# TSOC_ESP32S.net
KiCad netlist of a schematic drawn in EAGLE
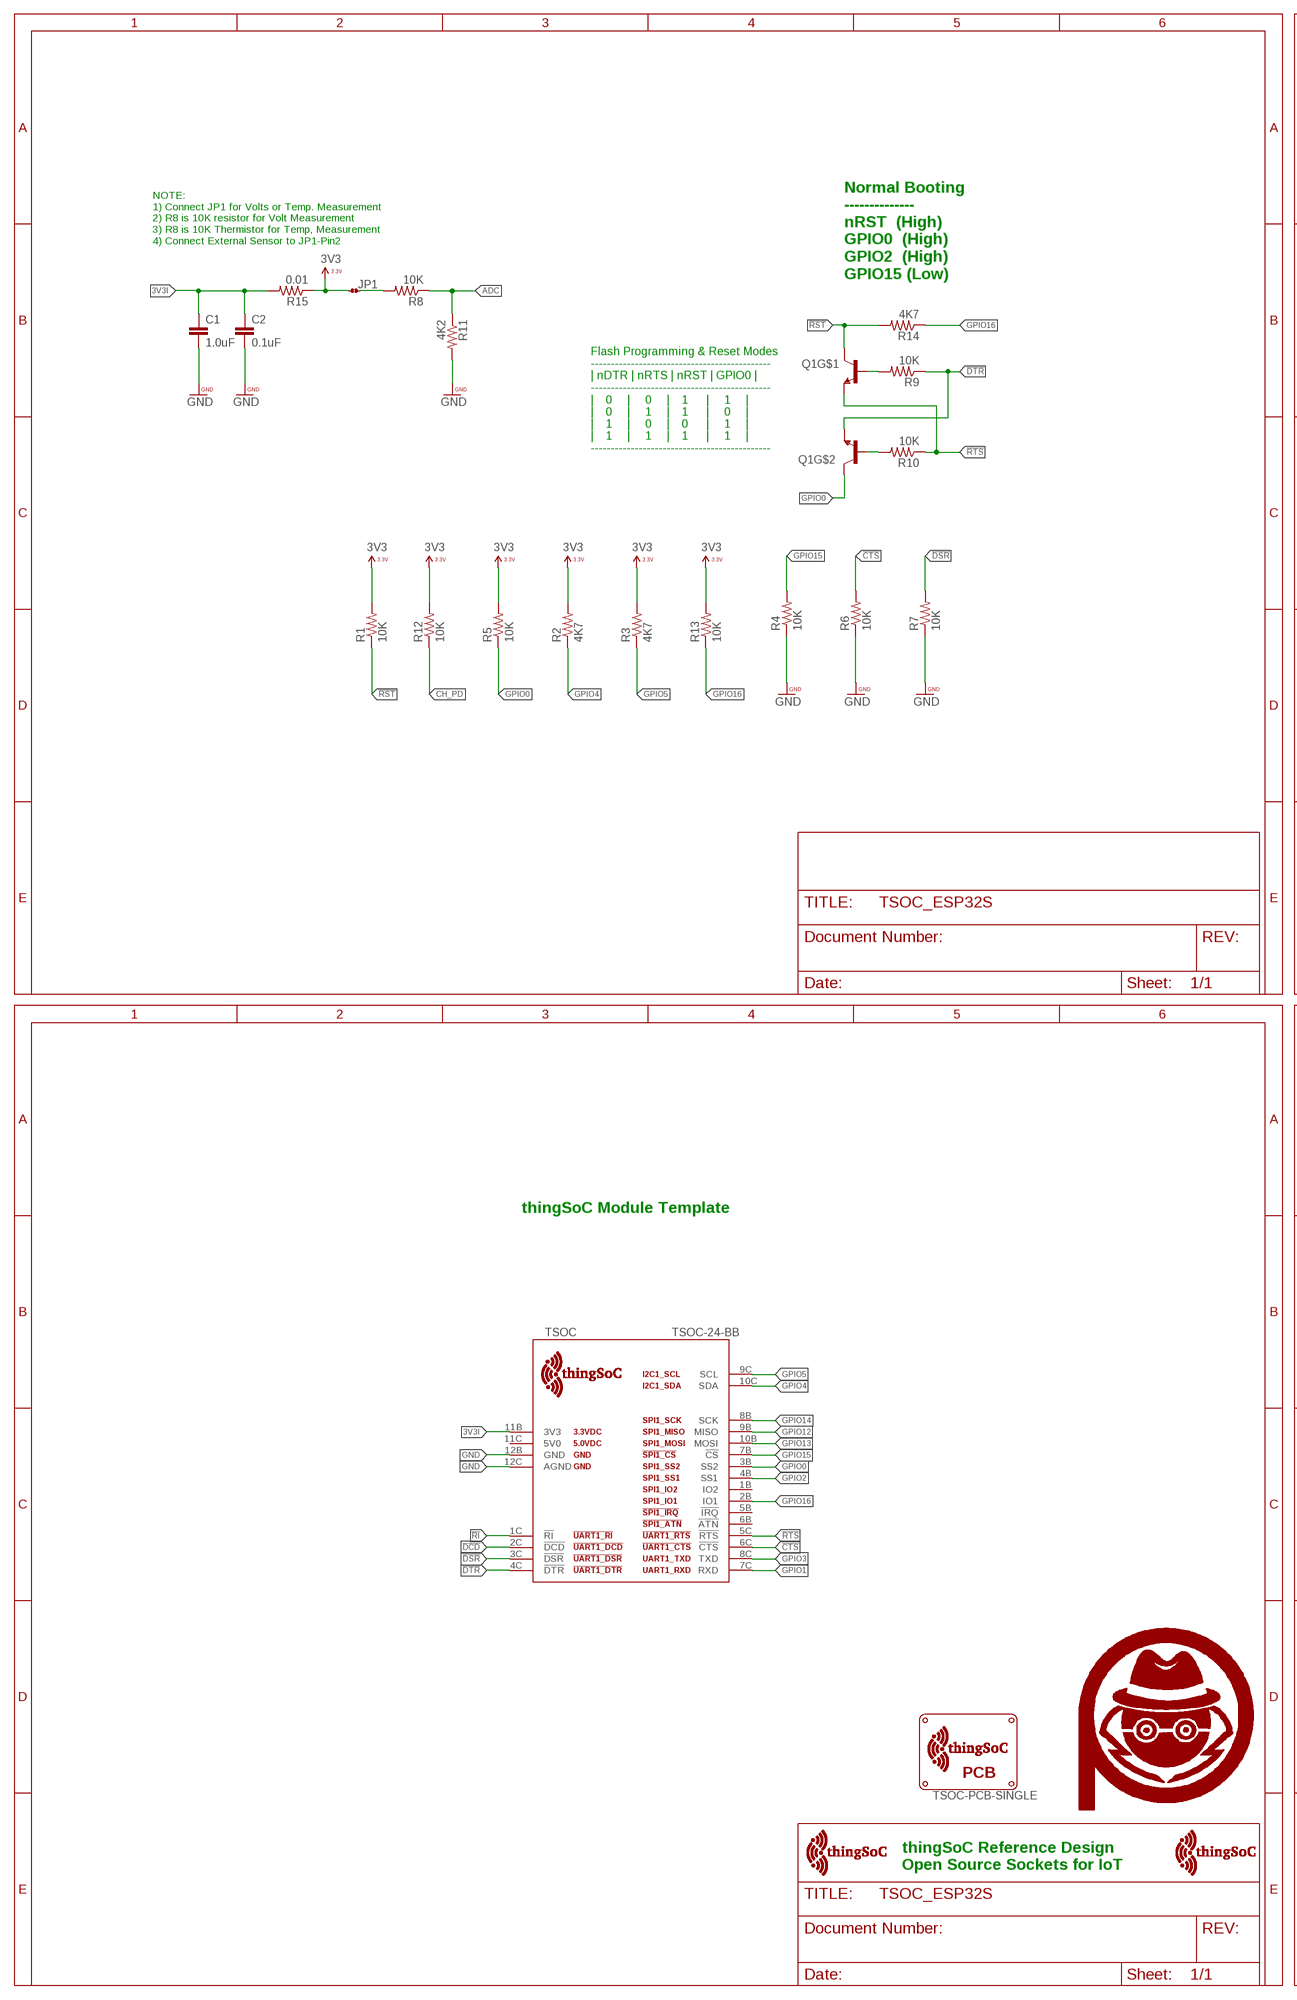
[diagram p0: schematic, sheet 1, part 1 of 2]
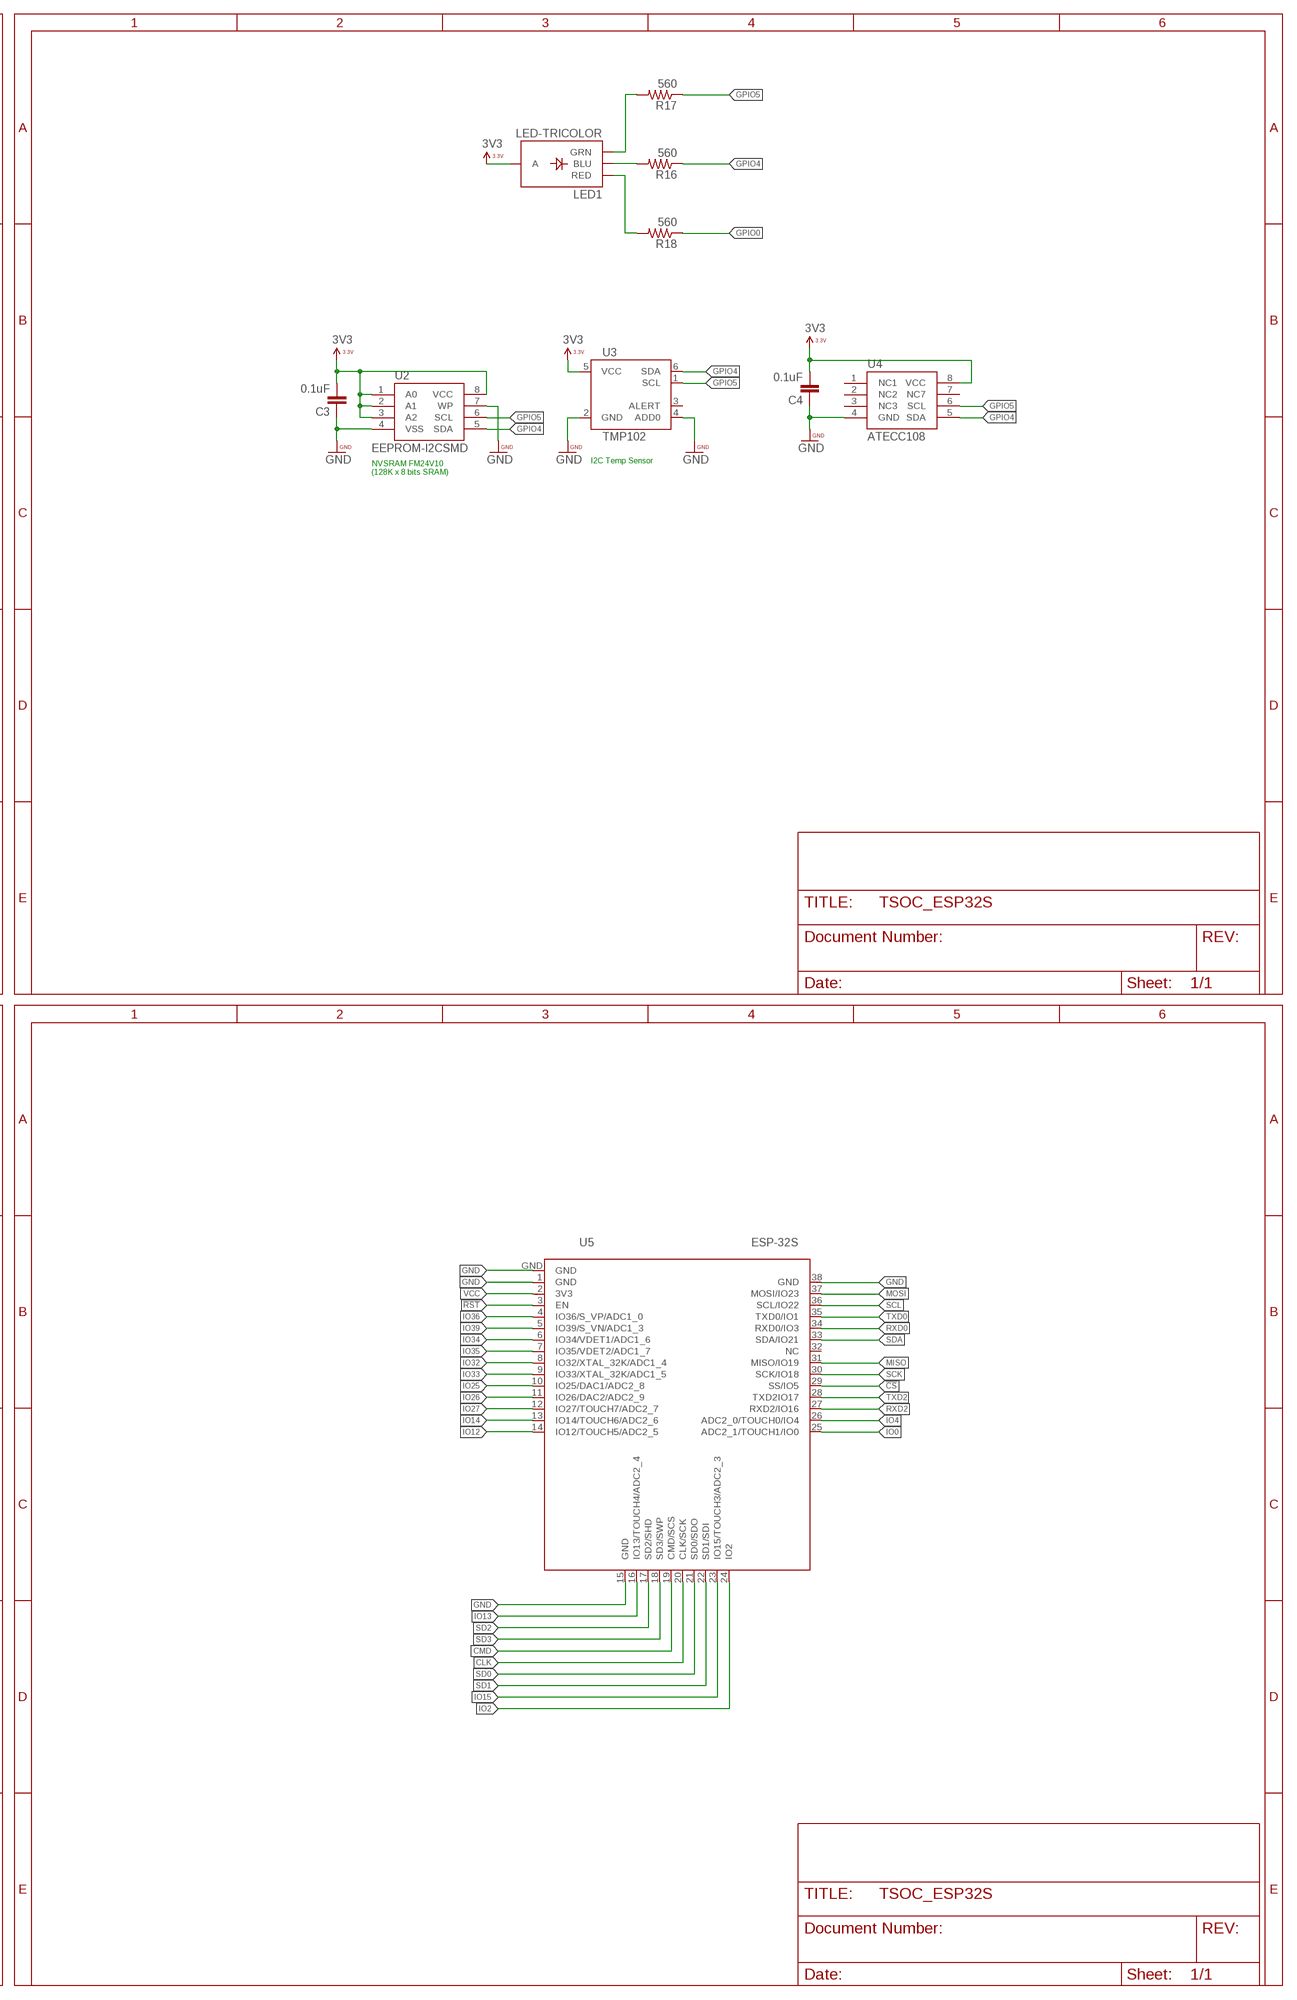
[diagram p1: schematic, sheet 1, part 2 of 2]

(export (version "E")
  (design (tool "Eeschema 10.0.6"))
  (components
    (comp (ref "C1")
      (value "1.0uF")
      (footprint "eagle-import:0402-CAP")
      (libsource (lib "eagle-import") (part "CAP0402-CAP"))
    )
    (comp (ref "C2")
      (value "0.1uF")
      (footprint "eagle-import:0402-CAP")
      (libsource (lib "eagle-import") (part "CAP0402-CAP"))
    )
    (comp (ref "C3")
      (value "0.1uF")
      (footprint "eagle-import:0402-CAP")
      (libsource (lib "eagle-import") (part "CAP0402-CAP"))
    )
    (comp (ref "C4")
      (value "0.1uF")
      (footprint "eagle-import:0402-CAP")
      (libsource (lib "eagle-import") (part "CAP0402-CAP"))
    )
    (comp (ref "JP1")
      (value "JMP-2-NO-0402")
      (footprint "eagle-import:JMP-2-NO-0402")
      (libsource (lib "eagle-import") (part "JMP-2-NO-0402"))
    )
    (comp (ref "LED1")
      (value "LED-TRICOLOR")
      (footprint "eagle-import:LED-TRICOLOR-SMD")
      (libsource (lib "eagle-import") (part "LED-TRICOLOR"))
    )
    (comp (ref "Q1")
      (value "MMBT2222A")
      (footprint "eagle-import:SOT363")
      (libsource (lib "eagle-import") (part "MMDT3904"))
    )
    (comp (ref "R1")
      (value "10K")
      (footprint "eagle-import:0402-RES")
      (libsource (lib "eagle-import") (part "RESISTOR0402"))
    )
    (comp (ref "R2")
      (value "4K7")
      (footprint "eagle-import:0402-RES")
      (libsource (lib "eagle-import") (part "RESISTOR0402"))
    )
    (comp (ref "R3")
      (value "4K7")
      (footprint "eagle-import:0402-RES")
      (libsource (lib "eagle-import") (part "RESISTOR0402"))
    )
    (comp (ref "R4")
      (value "10K")
      (footprint "eagle-import:0402-RES")
      (libsource (lib "eagle-import") (part "RESISTOR0402"))
    )
    (comp (ref "R5")
      (value "10K")
      (footprint "eagle-import:0402-RES")
      (libsource (lib "eagle-import") (part "RESISTOR0402"))
    )
    (comp (ref "R6")
      (value "10K")
      (footprint "eagle-import:0402-RES")
      (libsource (lib "eagle-import") (part "RESISTOR0402"))
    )
    (comp (ref "R7")
      (value "10K")
      (footprint "eagle-import:0402-RES")
      (libsource (lib "eagle-import") (part "RESISTOR0402"))
    )
    (comp (ref "R8")
      (value "10K")
      (footprint "eagle-import:0402-RES")
      (libsource (lib "eagle-import") (part "RESISTOR0402"))
    )
    (comp (ref "R9")
      (value "10K")
      (footprint "eagle-import:0402-RES")
      (libsource (lib "eagle-import") (part "RESISTOR0402"))
    )
    (comp (ref "R10")
      (value "10K")
      (footprint "eagle-import:0402-RES")
      (libsource (lib "eagle-import") (part "RESISTOR0402"))
    )
    (comp (ref "R11")
      (value "4K2")
      (footprint "eagle-import:0402-RES")
      (libsource (lib "eagle-import") (part "RESISTOR0402"))
    )
    (comp (ref "R12")
      (value "10K")
      (footprint "eagle-import:0402-RES")
      (libsource (lib "eagle-import") (part "RESISTOR0402"))
    )
    (comp (ref "R13")
      (value "10K")
      (footprint "eagle-import:0402-RES")
      (libsource (lib "eagle-import") (part "RESISTOR0402"))
    )
    (comp (ref "R14")
      (value "4K7")
      (footprint "eagle-import:0402-RES")
      (libsource (lib "eagle-import") (part "RESISTOR0402"))
    )
    (comp (ref "R15")
      (value "0.01")
      (footprint "eagle-import:0402-RES")
      (libsource (lib "eagle-import") (part "RESISTOR0402"))
    )
    (comp (ref "R16")
      (value "560")
      (footprint "eagle-import:0402-RES")
      (libsource (lib "eagle-import") (part "RESISTOR0402"))
    )
    (comp (ref "R17")
      (value "560")
      (footprint "eagle-import:0402-RES")
      (libsource (lib "eagle-import") (part "RESISTOR0402"))
    )
    (comp (ref "R18")
      (value "560")
      (footprint "eagle-import:0402-RES")
      (libsource (lib "eagle-import") (part "RESISTOR0402"))
    )
    (comp (ref "TSOC")
      (value "TSOC-24-BB")
      (footprint "eagle-import:TSOC-BB-S24")
      (libsource (lib "eagle-import") (part "TSOC-24-BB"))
    )
    (comp (ref "U$11")
      (value "PA_LOGO_SYMMED")
      (footprint "eagle-import:PA_LOGO_AGENT_MED_SYM")
      (libsource (lib "eagle-import") (part "PA_LOGO_SYMMED"))
    )
    (comp (ref "U$19")
      (value "TSOC-LOGO-MED")
      (footprint "eagle-import:TSOC-LOGO-MED")
      (libsource (lib "eagle-import") (part "TSOC-LOGO-MED"))
    )
    (comp (ref "U$20")
      (value "TSOC-LOGO-MED")
      (footprint "eagle-import:TSOC-LOGO-MED")
      (libsource (lib "eagle-import") (part "TSOC-LOGO-MED"))
    )
    (comp (ref "U$25")
      (value "TSOC-PCB-SINGLE")
      (footprint "eagle-import:TSOC-BB-BRD-DIM")
      (libsource (lib "eagle-import") (part "TSOC-PCB-SINGLE"))
    )
    (comp (ref "U2")
      (value "EEPROM-I2CSMD")
      (footprint "eagle-import:SO08")
      (libsource (lib "eagle-import") (part "EEPROM-I2CSMD"))
    )
    (comp (ref "U3")
      (value "TMP102")
      (footprint "eagle-import:SOT563")
      (libsource (lib "eagle-import") (part "TMP102"))
    )
    (comp (ref "U4")
      (value "ATECC108")
      (footprint "eagle-import:SOIC8")
      (libsource (lib "eagle-import") (part "ATECC108"))
    )
    (comp (ref "U5")
      (value "ESP-32S")
      (footprint "eagle-import:ESP-32S")
      (libsource (lib "eagle-import") (part "ESP-32S"))
    )
  )
  (nets
    (net (code "1") (name "/~{CS}") (class "Default")
      (node (ref "U5") (pin "29") (pinfunction "SS/IO5_29") (pintype "bidirectional"))
    )
    (net (code "2") (name "/~{CTS}") (class "Default")
      (node (ref "R6") (pin "2") (pinfunction "2_2") (pintype "passive"))
      (node (ref "TSOC") (pin "6C") (pinfunction "~{CTS}_6C") (pintype "bidirectional"))
    )
    (net (code "3") (name "/~{DCD}") (class "Default")
      (node (ref "TSOC") (pin "2C") (pinfunction "~{DCD}_2C") (pintype "bidirectional"))
    )
    (net (code "4") (name "/~{DSR}") (class "Default")
      (node (ref "R7") (pin "2") (pinfunction "2_2") (pintype "passive"))
      (node (ref "TSOC") (pin "3C") (pinfunction "~{DSR}_3C") (pintype "bidirectional"))
    )
    (net (code "5") (name "/~{DTR}") (class "Default")
      (node (ref "Q1") (pin "1") (pinfunction "E_1") (pintype "passive"))
      (node (ref "R9") (pin "1") (pinfunction "1_1") (pintype "passive"))
      (node (ref "TSOC") (pin "4C") (pinfunction "~{DTR}_4C") (pintype "bidirectional"))
    )
    (net (code "6") (name "/~{RI}") (class "Default")
      (node (ref "TSOC") (pin "1C") (pinfunction "~{RI}_1C") (pintype "bidirectional"))
    )
    (net (code "7") (name "/~{RST}") (class "Default")
      (node (ref "Q1") (pin "3") (pinfunction "C_3") (pintype "passive"))
      (node (ref "R1") (pin "1") (pinfunction "1_1") (pintype "passive"))
      (node (ref "R14") (pin "2") (pinfunction "2_2") (pintype "passive"))
      (node (ref "U5") (pin "3") (pinfunction "EN_3") (pintype "bidirectional"))
    )
    (net (code "8") (name "/~{RTS}") (class "Default")
      (node (ref "Q1") (pin "4") (pinfunction "E_4") (pintype "passive"))
      (node (ref "R10") (pin "1") (pinfunction "1_1") (pintype "passive"))
      (node (ref "TSOC") (pin "5C") (pinfunction "~{RTS}_5C") (pintype "bidirectional"))
    )
    (net (code "9") (name "3V3") (class "Default")
      (node (ref "C3") (pin "2") (pinfunction "2_2") (pintype "passive"))
      (node (ref "C4") (pin "2") (pinfunction "2_2") (pintype "passive"))
      (node (ref "JP1") (pin "1") (pinfunction "1_1") (pintype "passive"))
      (node (ref "LED1") (pin "A") (pinfunction "A_A") (pintype "bidirectional"))
      (node (ref "R1") (pin "2") (pinfunction "2_2") (pintype "passive"))
      (node (ref "R12") (pin "2") (pinfunction "2_2") (pintype "passive"))
      (node (ref "R13") (pin "2") (pinfunction "2_2") (pintype "passive"))
      (node (ref "R15") (pin "1") (pinfunction "1_1") (pintype "passive"))
      (node (ref "R2") (pin "2") (pinfunction "2_2") (pintype "passive"))
      (node (ref "R3") (pin "2") (pinfunction "2_2") (pintype "passive"))
      (node (ref "R5") (pin "2") (pinfunction "2_2") (pintype "passive"))
      (node (ref "U2") (pin "1") (pinfunction "A0_1") (pintype "bidirectional"))
      (node (ref "U2") (pin "2") (pinfunction "A1_2") (pintype "bidirectional"))
      (node (ref "U2") (pin "3") (pinfunction "A2_3") (pintype "bidirectional"))
      (node (ref "U2") (pin "8") (pinfunction "VCC_8") (pintype "power_in"))
      (node (ref "U3") (pin "5") (pinfunction "VCC_5") (pintype "bidirectional"))
      (node (ref "U4") (pin "8") (pinfunction "VCC_8") (pintype "power_in"))
    )
    (net (code "10") (name "3V3I") (class "Default")
      (node (ref "C1") (pin "1") (pinfunction "1_1") (pintype "passive"))
      (node (ref "C2") (pin "1") (pinfunction "1_1") (pintype "passive"))
      (node (ref "R15") (pin "2") (pinfunction "2_2") (pintype "passive"))
      (node (ref "TSOC") (pin "11B") (pinfunction "3V3_11B") (pintype "bidirectional"))
    )
    (net (code "11") (name "ADC") (class "Default")
      (node (ref "R11") (pin "1") (pinfunction "1_1") (pintype "passive"))
      (node (ref "R8") (pin "1") (pinfunction "1_1") (pintype "passive"))
    )
    (net (code "12") (name "CH_PD") (class "Default")
      (node (ref "R12") (pin "1") (pinfunction "1_1") (pintype "passive"))
    )
    (net (code "13") (name "CLK") (class "Default")
      (node (ref "U5") (pin "20") (pinfunction "CLK/SCK_20") (pintype "bidirectional"))
    )
    (net (code "14") (name "CMD") (class "Default")
      (node (ref "U5") (pin "19") (pinfunction "CMD/SCS_19") (pintype "bidirectional"))
    )
    (net (code "15") (name "GND") (class "Default")
      (node (ref "C1") (pin "2") (pinfunction "2_2") (pintype "passive"))
      (node (ref "C2") (pin "2") (pinfunction "2_2") (pintype "passive"))
      (node (ref "C3") (pin "1") (pinfunction "1_1") (pintype "passive"))
      (node (ref "C4") (pin "1") (pinfunction "1_1") (pintype "passive"))
      (node (ref "R11") (pin "2") (pinfunction "2_2") (pintype "passive"))
      (node (ref "R4") (pin "1") (pinfunction "1_1") (pintype "passive"))
      (node (ref "R6") (pin "1") (pinfunction "1_1") (pintype "passive"))
      (node (ref "R7") (pin "1") (pinfunction "1_1") (pintype "passive"))
      (node (ref "TSOC") (pin "12B") (pinfunction "GND_12B") (pintype "bidirectional"))
      (node (ref "TSOC") (pin "12C") (pinfunction "AGND_12C") (pintype "bidirectional"))
      (node (ref "U2") (pin "4") (pinfunction "VSS_4") (pintype "power_in"))
      (node (ref "U2") (pin "7") (pinfunction "WP_7") (pintype "bidirectional"))
      (node (ref "U3") (pin "2") (pinfunction "GND_2") (pintype "bidirectional"))
      (node (ref "U3") (pin "4") (pinfunction "ADD0_4") (pintype "bidirectional"))
      (node (ref "U4") (pin "4") (pinfunction "GND_4") (pintype "power_in"))
      (node (ref "U5") (pin "1") (pinfunction "GND_1") (pintype "bidirectional"))
      (node (ref "U5") (pin "15") (pinfunction "GND_15") (pintype "bidirectional"))
      (node (ref "U5") (pin "38") (pinfunction "GND_38") (pintype "bidirectional"))
      (node (ref "U5") (pin "GND") (pinfunction "GND_GND") (pintype "bidirectional"))
    )
    (net (code "16") (name "GPIO0") (class "Default")
      (node (ref "Q1") (pin "6") (pinfunction "C_6") (pintype "passive"))
      (node (ref "R18") (pin "1") (pinfunction "1_1") (pintype "passive"))
      (node (ref "R5") (pin "1") (pinfunction "1_1") (pintype "passive"))
      (node (ref "TSOC") (pin "3B") (pinfunction "SS2_3B") (pintype "bidirectional"))
    )
    (net (code "17") (name "GPIO1") (class "Default")
      (node (ref "TSOC") (pin "7C") (pinfunction "RXD_7C") (pintype "bidirectional"))
    )
    (net (code "18") (name "GPIO2") (class "Default")
      (node (ref "TSOC") (pin "4B") (pinfunction "SS1_4B") (pintype "bidirectional"))
    )
    (net (code "19") (name "GPIO3") (class "Default")
      (node (ref "TSOC") (pin "8C") (pinfunction "TXD_8C") (pintype "bidirectional"))
    )
    (net (code "20") (name "GPIO4") (class "Default")
      (node (ref "R16") (pin "1") (pinfunction "1_1") (pintype "passive"))
      (node (ref "R2") (pin "1") (pinfunction "1_1") (pintype "passive"))
      (node (ref "TSOC") (pin "10C") (pinfunction "SDA_10C") (pintype "bidirectional"))
      (node (ref "U2") (pin "5") (pinfunction "SDA_5") (pintype "bidirectional"))
      (node (ref "U3") (pin "6") (pinfunction "SDA_6") (pintype "bidirectional"))
      (node (ref "U4") (pin "5") (pinfunction "SDA_5") (pintype "bidirectional"))
    )
    (net (code "21") (name "GPIO5") (class "Default")
      (node (ref "R17") (pin "1") (pinfunction "1_1") (pintype "passive"))
      (node (ref "R3") (pin "1") (pinfunction "1_1") (pintype "passive"))
      (node (ref "TSOC") (pin "9C") (pinfunction "SCL_9C") (pintype "bidirectional"))
      (node (ref "U2") (pin "6") (pinfunction "SCL_6") (pintype "bidirectional"))
      (node (ref "U3") (pin "1") (pinfunction "SCL_1") (pintype "bidirectional"))
      (node (ref "U4") (pin "6") (pinfunction "SCL_6") (pintype "bidirectional"))
    )
    (net (code "22") (name "GPIO12") (class "Default")
      (node (ref "TSOC") (pin "9B") (pinfunction "MISO_9B") (pintype "bidirectional"))
    )
    (net (code "23") (name "GPIO13") (class "Default")
      (node (ref "TSOC") (pin "10B") (pinfunction "MOSI_10B") (pintype "bidirectional"))
    )
    (net (code "24") (name "GPIO14") (class "Default")
      (node (ref "TSOC") (pin "8B") (pinfunction "SCK_8B") (pintype "bidirectional"))
    )
    (net (code "25") (name "GPIO15") (class "Default")
      (node (ref "R4") (pin "2") (pinfunction "2_2") (pintype "passive"))
      (node (ref "TSOC") (pin "7B") (pinfunction "~{CS}_7B") (pintype "bidirectional"))
    )
    (net (code "26") (name "GPIO16") (class "Default")
      (node (ref "R13") (pin "1") (pinfunction "1_1") (pintype "passive"))
      (node (ref "R14") (pin "1") (pinfunction "1_1") (pintype "passive"))
      (node (ref "TSOC") (pin "2B") (pinfunction "IO1_2B") (pintype "bidirectional"))
    )
    (net (code "27") (name "IO0") (class "Default")
      (node (ref "U5") (pin "25") (pinfunction "ADC2_1/TOUCH1/IO0_25") (pintype "bidirectional"))
    )
    (net (code "28") (name "IO2") (class "Default")
      (node (ref "U5") (pin "24") (pinfunction "IO2_24") (pintype "bidirectional"))
    )
    (net (code "29") (name "IO4") (class "Default")
      (node (ref "U5") (pin "26") (pinfunction "ADC2_0/TOUCH0/IO4_26") (pintype "bidirectional"))
    )
    (net (code "30") (name "IO12") (class "Default")
      (node (ref "U5") (pin "14") (pinfunction "IO12/TOUCH5/ADC2_5_14") (pintype "bidirectional"))
    )
    (net (code "31") (name "IO13") (class "Default")
      (node (ref "U5") (pin "16") (pinfunction "IO13/TOUCH4/ADC2_4_16") (pintype "bidirectional"))
    )
    (net (code "32") (name "IO14") (class "Default")
      (node (ref "U5") (pin "13") (pinfunction "IO14/TOUCH6/ADC2_6_13") (pintype "bidirectional"))
    )
    (net (code "33") (name "IO15") (class "Default")
      (node (ref "U5") (pin "23") (pinfunction "IO15/TOUCH3/ADC2_3_23") (pintype "bidirectional"))
    )
    (net (code "34") (name "IO25") (class "Default")
      (node (ref "U5") (pin "10") (pinfunction "IO25/DAC1/ADC2_8_10") (pintype "bidirectional"))
    )
    (net (code "35") (name "IO26") (class "Default")
      (node (ref "U5") (pin "11") (pinfunction "IO26/DAC2/ADC2_9_11") (pintype "bidirectional"))
    )
    (net (code "36") (name "IO27") (class "Default")
      (node (ref "U5") (pin "12") (pinfunction "IO27/TOUCH7/ADC2_7_12") (pintype "bidirectional"))
    )
    (net (code "37") (name "IO32") (class "Default")
      (node (ref "U5") (pin "8") (pinfunction "IO32/XTAL_32K/ADC1_4_8") (pintype "bidirectional"))
    )
    (net (code "38") (name "IO33") (class "Default")
      (node (ref "U5") (pin "9") (pinfunction "IO33/XTAL_32K/ADC1_5_9") (pintype "bidirectional"))
    )
    (net (code "39") (name "IO34") (class "Default")
      (node (ref "U5") (pin "6") (pinfunction "IO34/VDET1/ADC1_6_6") (pintype "bidirectional"))
    )
    (net (code "40") (name "IO35") (class "Default")
      (node (ref "U5") (pin "7") (pinfunction "IO35/VDET2/ADC1_7_7") (pintype "bidirectional"))
    )
    (net (code "41") (name "IO36") (class "Default")
      (node (ref "U5") (pin "4") (pinfunction "IO36/S_VP/ADC1_0_4") (pintype "bidirectional"))
    )
    (net (code "42") (name "IO39") (class "Default")
      (node (ref "U5") (pin "5") (pinfunction "IO39/S_VN/ADC1_3_5") (pintype "bidirectional"))
    )
    (net (code "43") (name "MISO") (class "Default")
      (node (ref "U5") (pin "31") (pinfunction "MISO/IO19_31") (pintype "bidirectional"))
    )
    (net (code "44") (name "MOSI") (class "Default")
      (node (ref "U5") (pin "37") (pinfunction "MOSI/IO23_37") (pintype "bidirectional"))
    )
    (net (code "45") (name "Net-(JP1-Pad2)") (class "Default")
      (node (ref "JP1") (pin "2") (pinfunction "2_2") (pintype "passive"))
      (node (ref "R8") (pin "2") (pinfunction "2_2") (pintype "passive"))
    )
    (net (code "46") (name "Net-(LED1-BLU)") (class "Default")
      (node (ref "LED1") (pin "B") (pinfunction "BLU_B") (pintype "bidirectional"))
      (node (ref "R16") (pin "2") (pinfunction "2_2") (pintype "passive"))
    )
    (net (code "47") (name "Net-(LED1-GRN)") (class "Default")
      (node (ref "LED1") (pin "G") (pinfunction "GRN_G") (pintype "bidirectional"))
      (node (ref "R17") (pin "2") (pinfunction "2_2") (pintype "passive"))
    )
    (net (code "48") (name "Net-(LED1-RED)") (class "Default")
      (node (ref "LED1") (pin "R") (pinfunction "RED_R") (pintype "bidirectional"))
      (node (ref "R18") (pin "2") (pinfunction "2_2") (pintype "passive"))
    )
    (net (code "49") (name "Net-(Q1A-B)") (class "Default")
      (node (ref "Q1") (pin "5") (pinfunction "B_5") (pintype "passive"))
      (node (ref "R9") (pin "2") (pinfunction "2_2") (pintype "passive"))
    )
    (net (code "50") (name "Net-(Q1B-B)") (class "Default")
      (node (ref "Q1") (pin "2") (pinfunction "B_2") (pintype "passive"))
      (node (ref "R10") (pin "2") (pinfunction "2_2") (pintype "passive"))
    )
    (net (code "51") (name "RXD0") (class "Default")
      (node (ref "U5") (pin "34") (pinfunction "RXD0/IO3_34") (pintype "bidirectional"))
    )
    (net (code "52") (name "RXD2") (class "Default")
      (node (ref "U5") (pin "27") (pinfunction "RXD2/IO16_27") (pintype "bidirectional"))
    )
    (net (code "53") (name "SCK") (class "Default")
      (node (ref "U5") (pin "30") (pinfunction "SCK/IO18_30") (pintype "bidirectional"))
    )
    (net (code "54") (name "SCL") (class "Default")
      (node (ref "U5") (pin "36") (pinfunction "SCL/IO22_36") (pintype "bidirectional"))
    )
    (net (code "55") (name "SD0") (class "Default")
      (node (ref "U5") (pin "21") (pinfunction "SD0/SDO_21") (pintype "bidirectional"))
    )
    (net (code "56") (name "SD1") (class "Default")
      (node (ref "U5") (pin "22") (pinfunction "SD1/SDI_22") (pintype "bidirectional"))
    )
    (net (code "57") (name "SD2") (class "Default")
      (node (ref "U5") (pin "17") (pinfunction "SD2/SHD_17") (pintype "bidirectional"))
    )
    (net (code "58") (name "SD3") (class "Default")
      (node (ref "U5") (pin "18") (pinfunction "SD3/SWP_18") (pintype "bidirectional"))
    )
    (net (code "59") (name "SDA") (class "Default")
      (node (ref "U5") (pin "33") (pinfunction "SDA/IO21_33") (pintype "bidirectional"))
    )
    (net (code "60") (name "TXD0") (class "Default")
      (node (ref "U5") (pin "35") (pinfunction "TXD0/IO1_35") (pintype "bidirectional"))
    )
    (net (code "61") (name "TXD2") (class "Default")
      (node (ref "U5") (pin "28") (pinfunction "TXD2IO17_28") (pintype "bidirectional"))
    )
    (net (code "62") (name "VCC") (class "Default")
      (node (ref "U5") (pin "2") (pinfunction "3V3_2") (pintype "bidirectional"))
    )
    (net (code "63") (name "unconnected-(TSOC-5V0-Pad11C)") (class "Default")
      (node (ref "TSOC") (pin "11C") (pinfunction "5V0_11C") (pintype "bidirectional"))
    )
    (net (code "64") (name "unconnected-(TSOC-IO2-Pad1B)") (class "Default")
      (node (ref "TSOC") (pin "1B") (pinfunction "IO2_1B") (pintype "bidirectional"))
    )
    (net (code "65") (name "unconnected-(TSOC-~{ATN}-Pad6B)") (class "Default")
      (node (ref "TSOC") (pin "6B") (pinfunction "~{ATN}_6B") (pintype "bidirectional"))
    )
    (net (code "66") (name "unconnected-(TSOC-~{IRQ}-Pad5B)") (class "Default")
      (node (ref "TSOC") (pin "5B") (pinfunction "~{IRQ}_5B") (pintype "bidirectional"))
    )
    (net (code "67") (name "unconnected-(U3-ALERT-Pad3)") (class "Default")
      (node (ref "U3") (pin "3") (pinfunction "ALERT_3") (pintype "bidirectional"))
    )
    (net (code "68") (name "unconnected-(U4-NC1-Pad1)") (class "Default")
      (node (ref "U4") (pin "1") (pinfunction "NC1_1") (pintype "bidirectional"))
    )
    (net (code "69") (name "unconnected-(U4-NC2-Pad2)") (class "Default")
      (node (ref "U4") (pin "2") (pinfunction "NC2_2") (pintype "no_connect"))
    )
    (net (code "70") (name "unconnected-(U4-NC3-Pad3)") (class "Default")
      (node (ref "U4") (pin "3") (pinfunction "NC3_3") (pintype "no_connect"))
    )
    (net (code "71") (name "unconnected-(U4-NC7-Pad7)") (class "Default")
      (node (ref "U4") (pin "7") (pinfunction "NC7_7") (pintype "no_connect"))
    )
    (net (code "72") (name "unconnected-(U5-NC-Pad32)") (class "Default")
      (node (ref "U5") (pin "32") (pinfunction "NC_32") (pintype "bidirectional"))
    )
  )
)
